# 4_Button_Array_LED.net
KiCad netlist of a schematic drawn in EAGLE
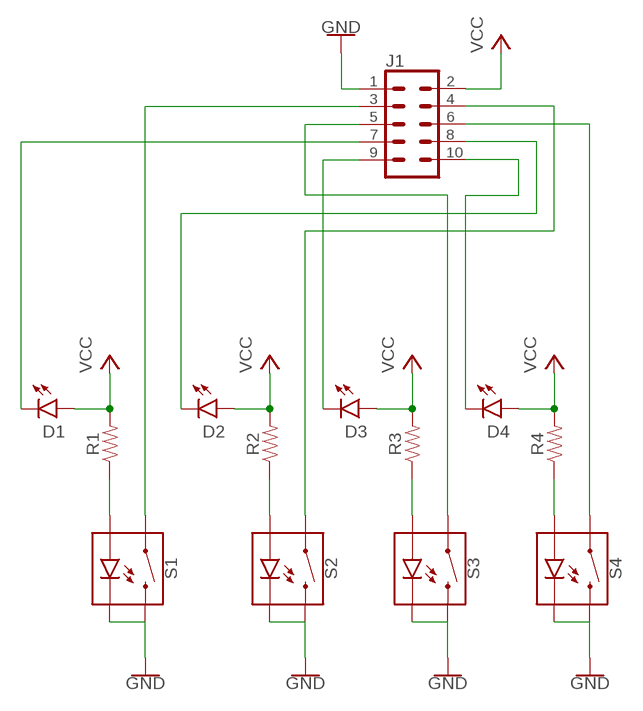
[diagram p0: schematic, sheet 1]

(export (version "E")
  (design (tool "Eeschema 10.0.6"))
  (components
    (comp (ref "D1")
      (value "LED3MM")
      (footprint "eagle-import:LED_3MM")
      (libsource (lib "eagle-import") (part "LED3MM"))
    )
    (comp (ref "D2")
      (value "LED3MM")
      (footprint "eagle-import:LED_3MM")
      (libsource (lib "eagle-import") (part "LED3MM"))
    )
    (comp (ref "D3")
      (value "LED3MM")
      (footprint "eagle-import:LED_3MM")
      (libsource (lib "eagle-import") (part "LED3MM"))
    )
    (comp (ref "D4")
      (value "LED3MM")
      (footprint "eagle-import:LED_3MM")
      (libsource (lib "eagle-import") (part "LED3MM"))
    )
    (comp (ref "J1")
      (value "CONN_05X2SHD-NS")
      (footprint "eagle-import:2X5-SHROUDED-NS")
      (libsource (lib "eagle-import") (part "CONN_05X2SHD-NS"))
    )
    (comp (ref "R1")
      (value "RESISTOR1206")
      (footprint "eagle-import:1206")
      (libsource (lib "eagle-import") (part "RESISTOR1206"))
    )
    (comp (ref "R2")
      (value "RESISTOR1206")
      (footprint "eagle-import:1206")
      (libsource (lib "eagle-import") (part "RESISTOR1206"))
    )
    (comp (ref "R3")
      (value "RESISTOR1206")
      (footprint "eagle-import:1206")
      (libsource (lib "eagle-import") (part "RESISTOR1206"))
    )
    (comp (ref "R4")
      (value "RESISTOR1206")
      (footprint "eagle-import:1206")
      (libsource (lib "eagle-import") (part "RESISTOR1206"))
    )
    (comp (ref "S1")
      (value "MOMENTARY-SWITCH-SPST-LED-PTH-12MM")
      (footprint "eagle-import:TACTILE_SWITCH_LED_PTH_12MM")
      (libsource (lib "eagle-import") (part "MOMENTARY-SWITCH-SPST-LED-PTH-12MM"))
    )
    (comp (ref "S2")
      (value "MOMENTARY-SWITCH-SPST-LED-PTH-12MM")
      (footprint "eagle-import:TACTILE_SWITCH_LED_PTH_12MM")
      (libsource (lib "eagle-import") (part "MOMENTARY-SWITCH-SPST-LED-PTH-12MM"))
    )
    (comp (ref "S3")
      (value "MOMENTARY-SWITCH-SPST-LED-PTH-12MM")
      (footprint "eagle-import:TACTILE_SWITCH_LED_PTH_12MM")
      (libsource (lib "eagle-import") (part "MOMENTARY-SWITCH-SPST-LED-PTH-12MM"))
    )
    (comp (ref "S4")
      (value "MOMENTARY-SWITCH-SPST-LED-PTH-12MM")
      (footprint "eagle-import:TACTILE_SWITCH_LED_PTH_12MM")
      (libsource (lib "eagle-import") (part "MOMENTARY-SWITCH-SPST-LED-PTH-12MM"))
    )
  )
  (nets
    (net (code "1") (name "GND") (class "Default")
      (node (ref "J1") (pin "1") (pinfunction "1_1") (pintype "passive"))
      (node (ref "S1") (pin "2") (pinfunction "2_2") (pintype "passive"))
      (node (ref "S1") (pin "C") (pinfunction "C_C") (pintype "passive"))
      (node (ref "S2") (pin "2") (pinfunction "2_2") (pintype "passive"))
      (node (ref "S2") (pin "C") (pinfunction "C_C") (pintype "passive"))
      (node (ref "S3") (pin "2") (pinfunction "2_2") (pintype "passive"))
      (node (ref "S3") (pin "C") (pinfunction "C_C") (pintype "passive"))
      (node (ref "S4") (pin "2") (pinfunction "2_2") (pintype "passive"))
      (node (ref "S4") (pin "C") (pinfunction "C_C") (pintype "passive"))
    )
    (net (code "2") (name "Net-(D1-C)") (class "Default")
      (node (ref "D1") (pin "K") (pinfunction "C_K") (pintype "passive"))
      (node (ref "J1") (pin "7") (pinfunction "7_7") (pintype "passive"))
    )
    (net (code "3") (name "Net-(D2-C)") (class "Default")
      (node (ref "D2") (pin "K") (pinfunction "C_K") (pintype "passive"))
      (node (ref "J1") (pin "8") (pinfunction "8_8") (pintype "passive"))
    )
    (net (code "4") (name "Net-(D3-C)") (class "Default")
      (node (ref "D3") (pin "K") (pinfunction "C_K") (pintype "passive"))
      (node (ref "J1") (pin "9") (pinfunction "9_9") (pintype "passive"))
    )
    (net (code "5") (name "Net-(D4-C)") (class "Default")
      (node (ref "D4") (pin "K") (pinfunction "C_K") (pintype "passive"))
      (node (ref "J1") (pin "10") (pinfunction "10_10") (pintype "passive"))
    )
    (net (code "6") (name "Net-(R1-Pad1)") (class "Default")
      (node (ref "R1") (pin "1") (pinfunction "1_1") (pintype "passive"))
      (node (ref "S1") (pin "A") (pinfunction "A_A") (pintype "passive"))
    )
    (net (code "7") (name "Net-(R2-Pad1)") (class "Default")
      (node (ref "R2") (pin "1") (pinfunction "1_1") (pintype "passive"))
      (node (ref "S2") (pin "A") (pinfunction "A_A") (pintype "passive"))
    )
    (net (code "8") (name "Net-(R3-Pad1)") (class "Default")
      (node (ref "R3") (pin "1") (pinfunction "1_1") (pintype "passive"))
      (node (ref "S3") (pin "A") (pinfunction "A_A") (pintype "passive"))
    )
    (net (code "9") (name "Net-(R4-Pad1)") (class "Default")
      (node (ref "R4") (pin "1") (pinfunction "1_1") (pintype "passive"))
      (node (ref "S4") (pin "A") (pinfunction "A_A") (pintype "passive"))
    )
    (net (code "10") (name "Net-(S1-1)") (class "Default")
      (node (ref "J1") (pin "3") (pinfunction "3_3") (pintype "passive"))
      (node (ref "S1") (pin "4") (pinfunction "1_4") (pintype "passive"))
    )
    (net (code "11") (name "Net-(S2-1)") (class "Default")
      (node (ref "J1") (pin "4") (pinfunction "4_4") (pintype "passive"))
      (node (ref "S2") (pin "4") (pinfunction "1_4") (pintype "passive"))
    )
    (net (code "12") (name "Net-(S3-1)") (class "Default")
      (node (ref "J1") (pin "5") (pinfunction "5_5") (pintype "passive"))
      (node (ref "S3") (pin "4") (pinfunction "1_4") (pintype "passive"))
    )
    (net (code "13") (name "Net-(S4-1)") (class "Default")
      (node (ref "J1") (pin "6") (pinfunction "6_6") (pintype "passive"))
      (node (ref "S4") (pin "4") (pinfunction "1_4") (pintype "passive"))
    )
    (net (code "14") (name "VCC") (class "Default")
      (node (ref "D1") (pin "A") (pinfunction "A_A") (pintype "passive"))
      (node (ref "D2") (pin "A") (pinfunction "A_A") (pintype "passive"))
      (node (ref "D3") (pin "A") (pinfunction "A_A") (pintype "passive"))
      (node (ref "D4") (pin "A") (pinfunction "A_A") (pintype "passive"))
      (node (ref "J1") (pin "2") (pinfunction "2_2") (pintype "passive"))
      (node (ref "R1") (pin "2") (pinfunction "2_2") (pintype "passive"))
      (node (ref "R2") (pin "2") (pinfunction "2_2") (pintype "passive"))
      (node (ref "R3") (pin "2") (pinfunction "2_2") (pintype "passive"))
      (node (ref "R4") (pin "2") (pinfunction "2_2") (pintype "passive"))
    )
  )
)
